# Sheet1.net
KiCad netlist of a schematic drawn in Altium Designer
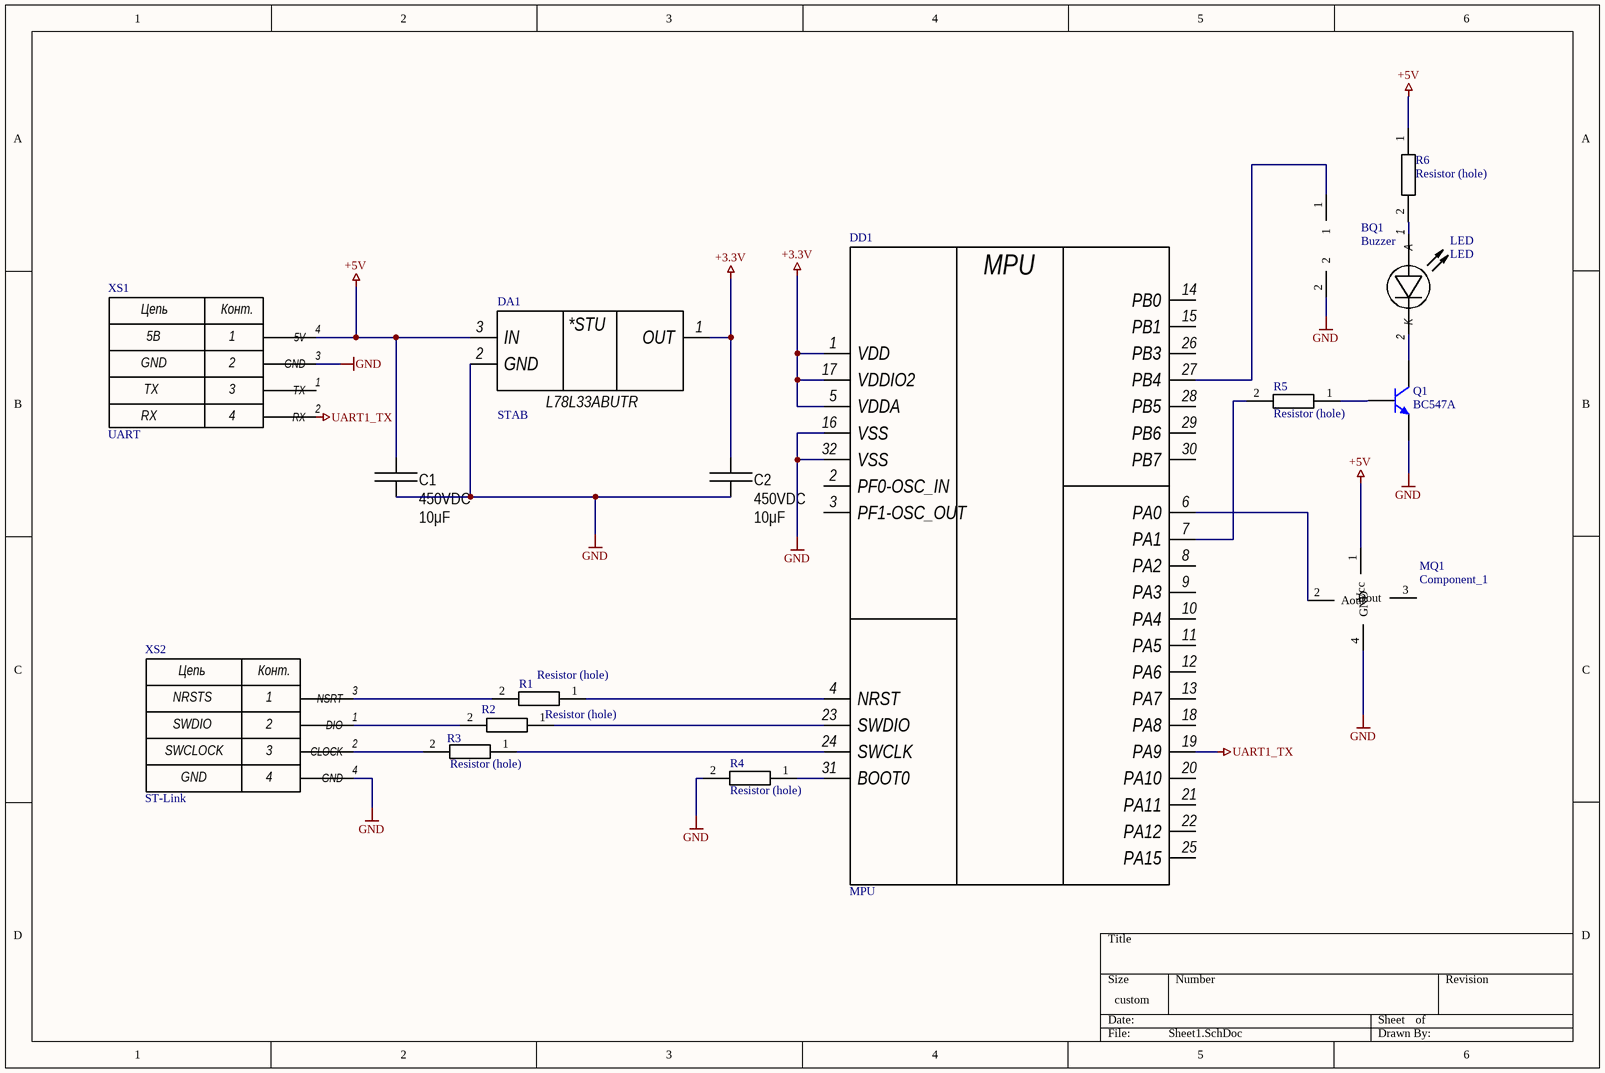
[diagram p0: Sheet1.SchDoc]

(export (version "E")
  (design (tool "Eeschema 10.0.6"))
  (components
    (comp (ref "BQ1") (value "Buzzer") (footprint "Buzzer 3V") (libsource (lib "Buzzer") (part "Buzzer")))
    (comp (ref "C1")
      (value "10μF")
      (footprint "CAP: AY2102M29Y5US63L7")
      (fields
        (field (name "MANUFACTURER") "Epcos")
        (field (name "PARTNUMBER") "B32774D4106K000")
        (field (name "VALUEMANUFACTURERPARTNUMBER") "Film capacitor, 10μF, 450VDC, ±10%, 10.9mOhm, 31.5x15 mm, -40...+105°C")
        (field (name "VOLTAGE") "450VDC")
      )
      (libsource (lib "Capacitor") (part "Film"))
    )
    (comp (ref "C2")
      (value "10μF")
      (footprint "CAP: AY2102M29Y5US63L7")
      (fields
        (field (name "MANUFACTURER") "Epcos")
        (field (name "PARTNUMBER") "B32774D4106K000")
        (field (name "VALUEMANUFACTURERPARTNUMBER") "Film capacitor, 10μF, 450VDC, ±10%, 10.9mOhm, 31.5x15 mm, -40...+105°C")
        (field (name "VOLTAGE") "450VDC")
      )
      (libsource (lib "Capacitor") (part "Film"))
    )
    (comp (ref "DA1") (value "STAB") (footprint "STAB") (libsource (lib "LibKurs2") (part "STAB")))
    (comp (ref "DD1") (value "MPU") (footprint "PCBComponent_1") (libsource (lib "MCU") (part "Component_1")))
    (comp (ref "LED") (value "LED") (footprint "LED") (libsource (lib "LibKurs2") (part "LED")))
    (comp (ref "MQ1")
      (value "Component_1")
      (footprint "Sensor")
      (libsource (lib "Sensor") (part "Component_1"))
    )
    (comp (ref "Q1")
      (value "BC547A")
      (footprint "TO-92A")
      (description "NPN General Purpose Amplifier")
      (fields (field (name "PUBLISHER") "Altium Limited"))
      (libsource (lib "Miscellaneous Devices") (part "2N3904"))
    )
    (comp (ref "R1")
      (value "Resistor (hole)")
      (footprint "Resistor 22")
      (libsource (lib "LibKurs2") (part "Resistor (hole)"))
    )
    (comp (ref "R2")
      (value "Resistor (hole)")
      (footprint "Resistor 22")
      (libsource (lib "LibKurs2") (part "Resistor (hole)"))
    )
    (comp (ref "R3")
      (value "Resistor (hole)")
      (footprint "Resistor 22")
      (libsource (lib "LibKurs2") (part "Resistor (hole)"))
    )
    (comp (ref "R4")
      (value "Resistor (hole)")
      (footprint "Resistor 22")
      (libsource (lib "LibKurs2") (part "Resistor (hole)"))
    )
    (comp (ref "R5")
      (value "Resistor (hole)")
      (footprint "Resistor 22")
      (libsource (lib "LibKurs2") (part "Resistor (hole)"))
    )
    (comp (ref "R6")
      (value "Resistor (hole)")
      (footprint "Resistor 22")
      (libsource (lib "") (part "Resistor (hole)_1"))
    )
    (comp (ref "XS1") (value "UART") (footprint "UART") (libsource (lib "LibKurs2") (part "UART")))
    (comp (ref "XS2") (value "ST-Link") (footprint "ST_Link") (libsource (lib "LibKurs2") (part "ST-Link")))
  )
  (nets
    (net (code "1") (name "+3.3V") (class "Default")
      (node (ref "C2") (pin "1") (pinfunction "1_1") (pintype "power_in"))
      (node (ref "DA1") (pin "1") (pinfunction "OUT_1") (pintype "power_in"))
      (node (ref "DD1") (pin "1") (pinfunction "VDD_1") (pintype "power_in"))
      (node (ref "DD1") (pin "17") (pinfunction "VDDIO2_17") (pintype "power_in"))
      (node (ref "DD1") (pin "5") (pinfunction "VDDA_5") (pintype "power_in"))
    )
    (net (code "2") (name "+5V") (class "Default")
      (node (ref "C1") (pin "1") (pinfunction "1_1") (pintype "power_in"))
      (node (ref "DA1") (pin "3") (pinfunction "IN_3") (pintype "power_in"))
      (node (ref "MQ1") (pin "1") (pinfunction "Vcc_1") (pintype "passive"))
      (node (ref "R6") (pin "1") (pinfunction "1_1") (pintype "passive"))
      (node (ref "XS1") (pin "4") (pinfunction "5V_4") (pintype "passive"))
    )
    (net (code "3") (name "GND") (class "Default")
      (node (ref "BQ1") (pin "2") (pinfunction "2_2") (pintype "passive"))
      (node (ref "C1") (pin "2") (pinfunction "2_2") (pintype "power_in"))
      (node (ref "C2") (pin "2") (pinfunction "2_2") (pintype "power_in"))
      (node (ref "DA1") (pin "2") (pinfunction "GND_2") (pintype "power_in"))
      (node (ref "DD1") (pin "16") (pinfunction "VSS_16") (pintype "power_in"))
      (node (ref "DD1") (pin "32") (pinfunction "VSS_32") (pintype "power_in"))
      (node (ref "MQ1") (pin "4") (pinfunction "GND_4") (pintype "passive"))
      (node (ref "Q1") (pin "1") (pinfunction "E_1") (pintype "passive"))
      (node (ref "R4") (pin "2") (pinfunction "2_2") (pintype "passive"))
      (node (ref "XS1") (pin "3") (pinfunction "GND_3") (pintype "passive"))
      (node (ref "XS2") (pin "4") (pinfunction "GND_4") (pintype "passive"))
    )
    (net (code "4") (name "Net-(DD1-BOOT0)") (class "Default")
      (node (ref "DD1") (pin "31") (pinfunction "BOOT0_31") (pintype "power_in"))
      (node (ref "R4") (pin "1") (pinfunction "1_1") (pintype "passive"))
    )
    (net (code "5") (name "Net-(DD1-NRST)") (class "Default")
      (node (ref "DD1") (pin "4") (pinfunction "NRST_4") (pintype "power_in"))
      (node (ref "R1") (pin "1") (pinfunction "1_1") (pintype "passive"))
    )
    (net (code "6") (name "Net-(DD1-PA0)") (class "Default")
      (node (ref "DD1") (pin "6") (pinfunction "PA0_6") (pintype "power_in"))
      (node (ref "MQ1") (pin "2") (pinfunction "Aout_2") (pintype "passive"))
    )
    (net (code "7") (name "Net-(DD1-PA1)") (class "Default")
      (node (ref "DD1") (pin "7") (pinfunction "PA1_7") (pintype "power_in"))
      (node (ref "R5") (pin "2") (pinfunction "2_2") (pintype "passive"))
    )
    (net (code "8") (name "Net-(DD1-PB4)") (class "Default")
      (node (ref "BQ1") (pin "1") (pinfunction "1_1") (pintype "passive"))
      (node (ref "DD1") (pin "27") (pinfunction "PB4_27") (pintype "power_in"))
    )
    (net (code "9") (name "Net-(DD1-SWCLK)") (class "Default")
      (node (ref "DD1") (pin "24") (pinfunction "SWCLK_24") (pintype "power_in"))
      (node (ref "R3") (pin "1") (pinfunction "1_1") (pintype "passive"))
    )
    (net (code "10") (name "Net-(DD1-SWDIO)") (class "Default")
      (node (ref "DD1") (pin "23") (pinfunction "SWDIO_23") (pintype "power_in"))
      (node (ref "R2") (pin "1") (pinfunction "1_1") (pintype "passive"))
    )
    (net (code "11") (name "Net-(LED-A)") (class "Default")
      (node (ref "LED") (pin "1") (pinfunction "A_1") (pintype "passive"))
      (node (ref "R6") (pin "2") (pinfunction "2_2") (pintype "passive"))
    )
    (net (code "12") (name "Net-(LED-K)") (class "Default")
      (node (ref "LED") (pin "2") (pinfunction "K_2") (pintype "passive"))
      (node (ref "Q1") (pin "3") (pinfunction "C_3") (pintype "passive"))
    )
    (net (code "13") (name "Net-(Q1-B)") (class "Default")
      (node (ref "Q1") (pin "2") (pinfunction "B_2") (pintype "passive"))
      (node (ref "R5") (pin "1") (pinfunction "1_1") (pintype "passive"))
    )
    (net (code "14") (name "Net-(XS2-CLOCK)") (class "Default")
      (node (ref "R3") (pin "2") (pinfunction "2_2") (pintype "passive"))
      (node (ref "XS2") (pin "2") (pinfunction "CLOCK_2") (pintype "passive"))
    )
    (net (code "15") (name "Net-(XS2-DIO)") (class "Default")
      (node (ref "R2") (pin "2") (pinfunction "2_2") (pintype "passive"))
      (node (ref "XS2") (pin "1") (pinfunction "DIO_1") (pintype "passive"))
    )
    (net (code "16") (name "Net-(XS2-NSRT)") (class "Default")
      (node (ref "R1") (pin "2") (pinfunction "2_2") (pintype "passive"))
      (node (ref "XS2") (pin "3") (pinfunction "NSRT_3") (pintype "passive"))
    )
    (net (code "17") (name "UART1_TX") (class "Default")
      (node (ref "DD1") (pin "19") (pinfunction "PA9_19") (pintype "power_in"))
      (node (ref "XS1") (pin "2") (pinfunction "RX_2") (pintype "passive"))
    )
    (net (code "18") (name "unconnected-(DD1-PA2-Pad8)") (class "Default")
      (node (ref "DD1") (pin "8") (pinfunction "PA2_8") (pintype "power_in"))
    )
    (net (code "19") (name "unconnected-(DD1-PA3-Pad9)") (class "Default")
      (node (ref "DD1") (pin "9") (pinfunction "PA3_9") (pintype "power_in"))
    )
    (net (code "20") (name "unconnected-(DD1-PA4-Pad10)") (class "Default")
      (node (ref "DD1") (pin "10") (pinfunction "PA4_10") (pintype "power_in"))
    )
    (net (code "21") (name "unconnected-(DD1-PA5-Pad11)") (class "Default")
      (node (ref "DD1") (pin "11") (pinfunction "PA5_11") (pintype "power_in"))
    )
    (net (code "22") (name "unconnected-(DD1-PA6-Pad12)") (class "Default")
      (node (ref "DD1") (pin "12") (pinfunction "PA6_12") (pintype "power_in"))
    )
    (net (code "23") (name "unconnected-(DD1-PA7-Pad13)") (class "Default")
      (node (ref "DD1") (pin "13") (pinfunction "PA7_13") (pintype "power_in"))
    )
    (net (code "24") (name "unconnected-(DD1-PA8-Pad18)") (class "Default")
      (node (ref "DD1") (pin "18") (pinfunction "PA8_18") (pintype "power_in"))
    )
    (net (code "25") (name "unconnected-(DD1-PA10-Pad20)") (class "Default")
      (node (ref "DD1") (pin "20") (pinfunction "PA10_20") (pintype "power_in"))
    )
    (net (code "26") (name "unconnected-(DD1-PA11-Pad21)") (class "Default")
      (node (ref "DD1") (pin "21") (pinfunction "PA11_21") (pintype "power_in"))
    )
    (net (code "27") (name "unconnected-(DD1-PA12-Pad22)") (class "Default")
      (node (ref "DD1") (pin "22") (pinfunction "PA12_22") (pintype "power_in"))
    )
    (net (code "28") (name "unconnected-(DD1-PA15-Pad25)") (class "Default")
      (node (ref "DD1") (pin "25") (pinfunction "PA15_25") (pintype "power_in"))
    )
    (net (code "29") (name "unconnected-(DD1-PB0-Pad14)") (class "Default")
      (node (ref "DD1") (pin "14") (pinfunction "PB0_14") (pintype "power_in"))
    )
    (net (code "30") (name "unconnected-(DD1-PB1-Pad15)") (class "Default")
      (node (ref "DD1") (pin "15") (pinfunction "PB1_15") (pintype "power_in"))
    )
    (net (code "31") (name "unconnected-(DD1-PB3-Pad26)") (class "Default")
      (node (ref "DD1") (pin "26") (pinfunction "PB3_26") (pintype "power_in"))
    )
    (net (code "32") (name "unconnected-(DD1-PB5-Pad28)") (class "Default")
      (node (ref "DD1") (pin "28") (pinfunction "PB5_28") (pintype "power_in"))
    )
    (net (code "33") (name "unconnected-(DD1-PB6-Pad29)") (class "Default")
      (node (ref "DD1") (pin "29") (pinfunction "PB6_29") (pintype "power_in"))
    )
    (net (code "34") (name "unconnected-(DD1-PB7-Pad30)") (class "Default")
      (node (ref "DD1") (pin "30") (pinfunction "PB7_30") (pintype "power_in"))
    )
    (net (code "35") (name "unconnected-(DD1-PF0-OSC_IN-Pad2)") (class "Default")
      (node (ref "DD1") (pin "2") (pinfunction "PF0-OSC_IN_2") (pintype "power_in"))
    )
    (net (code "36") (name "unconnected-(DD1-PF1-OSC_OUT-Pad3)") (class "Default")
      (node (ref "DD1") (pin "3") (pinfunction "PF1-OSC_OUT_3") (pintype "power_in"))
    )
    (net (code "37") (name "unconnected-(MQ1-Dout-Pad3)") (class "Default")
      (node (ref "MQ1") (pin "3") (pinfunction "Dout_3") (pintype "passive"))
    )
    (net (code "38") (name "unconnected-(XS1-TX-Pad1)") (class "Default")
      (node (ref "XS1") (pin "1") (pinfunction "TX_1") (pintype "passive"))
    )
  )
)
